# schematic.net
KiCad netlist of a schematic drawn in EAGLE
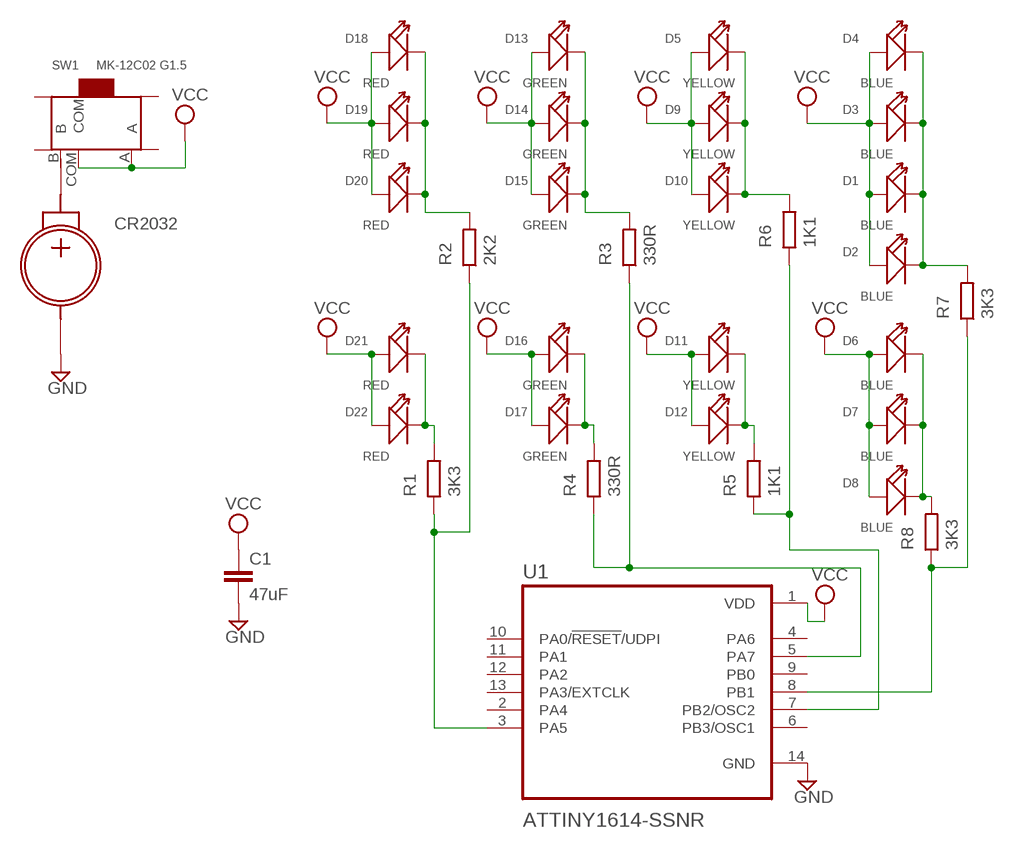
[diagram p0: schematic, sheet 1]

(export (version "E")
  (design (tool "Eeschema 10.0.6"))
  (components
    (comp (ref "C1")
      (value "47uF")
      (footprint "eagle-import:C1206")
      (libsource (lib "eagle-import") (part "C-EUC1206"))
    )
    (comp (ref "CR2032")
      (value "BS-7CR2032_COIN_CELL_BATTERY_HOLDER")
      (footprint "eagle-import:BS-7")
      (fields (field (name "MF") "MPD") (field (name "MP") "BS-7"))
      (libsource (lib "eagle-import") (part "BS-7CR2032_COIN_CELL_BATTERY_HOLDER"))
    )
    (comp (ref "D1")
      (value "BLUE")
      (footprint "eagle-import:LED2-2.54-D3.0MM")
      (fields (field (name "MPN") "CX-G302DC"))
      (libsource (lib "eagle-import") (part "DIP-LED-GREEN-GREEN(2P-D3MM)"))
    )
    (comp (ref "D2")
      (value "BLUE")
      (footprint "eagle-import:LED2-2.54-D3.0MM")
      (fields (field (name "MPN") "CX-G302DC"))
      (libsource (lib "eagle-import") (part "DIP-LED-GREEN-GREEN(2P-D3MM)"))
    )
    (comp (ref "D3")
      (value "BLUE")
      (footprint "eagle-import:LED2-2.54-D3.0MM")
      (fields (field (name "MPN") "CX-G302DC"))
      (libsource (lib "eagle-import") (part "DIP-LED-GREEN-GREEN(2P-D3MM)"))
    )
    (comp (ref "D4")
      (value "BLUE")
      (footprint "eagle-import:LED2-2.54-D3.0MM")
      (fields (field (name "MPN") "CX-G302DC"))
      (libsource (lib "eagle-import") (part "DIP-LED-GREEN-GREEN(2P-D3MM)"))
    )
    (comp (ref "D5")
      (value "YELLOW")
      (footprint "eagle-import:LED2-2.54-D3.0MM")
      (fields (field (name "MPN") "CX-G302DC"))
      (libsource (lib "eagle-import") (part "DIP-LED-GREEN-GREEN(2P-D3MM)"))
    )
    (comp (ref "D6")
      (value "BLUE")
      (footprint "eagle-import:LED2-2.54-D3.0MM")
      (fields (field (name "MPN") "CX-G302DC"))
      (libsource (lib "eagle-import") (part "DIP-LED-GREEN-GREEN(2P-D3MM)"))
    )
    (comp (ref "D7")
      (value "BLUE")
      (footprint "eagle-import:LED2-2.54-D3.0MM")
      (fields (field (name "MPN") "CX-G302DC"))
      (libsource (lib "eagle-import") (part "DIP-LED-GREEN-GREEN(2P-D3MM)"))
    )
    (comp (ref "D8")
      (value "BLUE")
      (footprint "eagle-import:LED2-2.54-D3.0MM")
      (fields (field (name "MPN") "CX-G302DC"))
      (libsource (lib "eagle-import") (part "DIP-LED-GREEN-GREEN(2P-D3MM)"))
    )
    (comp (ref "D9")
      (value "YELLOW")
      (footprint "eagle-import:LED2-2.54-D3.0MM")
      (fields (field (name "MPN") "CX-G302DC"))
      (libsource (lib "eagle-import") (part "DIP-LED-GREEN-GREEN(2P-D3MM)"))
    )
    (comp (ref "D10")
      (value "YELLOW")
      (footprint "eagle-import:LED2-2.54-D3.0MM")
      (fields (field (name "MPN") "CX-G302DC"))
      (libsource (lib "eagle-import") (part "DIP-LED-GREEN-GREEN(2P-D3MM)"))
    )
    (comp (ref "D11")
      (value "YELLOW")
      (footprint "eagle-import:LED2-2.54-D3.0MM")
      (fields (field (name "MPN") "CX-G302DC"))
      (libsource (lib "eagle-import") (part "DIP-LED-GREEN-GREEN(2P-D3MM)"))
    )
    (comp (ref "D12")
      (value "YELLOW")
      (footprint "eagle-import:LED2-2.54-D3.0MM")
      (fields (field (name "MPN") "CX-G302DC"))
      (libsource (lib "eagle-import") (part "DIP-LED-GREEN-GREEN(2P-D3MM)"))
    )
    (comp (ref "D13")
      (value "GREEN")
      (footprint "eagle-import:LED2-2.54-D3.0MM")
      (fields (field (name "MPN") "CX-G302DC"))
      (libsource (lib "eagle-import") (part "DIP-LED-GREEN-GREEN(2P-D3MM)"))
    )
    (comp (ref "D14")
      (value "GREEN")
      (footprint "eagle-import:LED2-2.54-D3.0MM")
      (fields (field (name "MPN") "CX-G302DC"))
      (libsource (lib "eagle-import") (part "DIP-LED-GREEN-GREEN(2P-D3MM)"))
    )
    (comp (ref "D15")
      (value "GREEN")
      (footprint "eagle-import:LED2-2.54-D3.0MM")
      (fields (field (name "MPN") "CX-G302DC"))
      (libsource (lib "eagle-import") (part "DIP-LED-GREEN-GREEN(2P-D3MM)"))
    )
    (comp (ref "D16")
      (value "GREEN")
      (footprint "eagle-import:LED2-2.54-D3.0MM")
      (fields (field (name "MPN") "CX-G302DC"))
      (libsource (lib "eagle-import") (part "DIP-LED-GREEN-GREEN(2P-D3MM)"))
    )
    (comp (ref "D17")
      (value "GREEN")
      (footprint "eagle-import:LED2-2.54-D3.0MM")
      (fields (field (name "MPN") "CX-G302DC"))
      (libsource (lib "eagle-import") (part "DIP-LED-GREEN-GREEN(2P-D3MM)"))
    )
    (comp (ref "D18")
      (value "RED")
      (footprint "eagle-import:LED2-2.54-D3.0MM")
      (fields (field (name "MPN") "CX-G302DC"))
      (libsource (lib "eagle-import") (part "DIP-LED-GREEN-GREEN(2P-D3MM)"))
    )
    (comp (ref "D19")
      (value "RED")
      (footprint "eagle-import:LED2-2.54-D3.0MM")
      (fields (field (name "MPN") "CX-G302DC"))
      (libsource (lib "eagle-import") (part "DIP-LED-GREEN-GREEN(2P-D3MM)"))
    )
    (comp (ref "D20")
      (value "RED")
      (footprint "eagle-import:LED2-2.54-D3.0MM")
      (fields (field (name "MPN") "CX-G302DC"))
      (libsource (lib "eagle-import") (part "DIP-LED-GREEN-GREEN(2P-D3MM)"))
    )
    (comp (ref "D21")
      (value "RED")
      (footprint "eagle-import:LED2-2.54-D3.0MM")
      (fields (field (name "MPN") "CX-G302DC"))
      (libsource (lib "eagle-import") (part "DIP-LED-GREEN-GREEN(2P-D3MM)"))
    )
    (comp (ref "D22")
      (value "RED")
      (footprint "eagle-import:LED2-2.54-D3.0MM")
      (fields (field (name "MPN") "CX-G302DC"))
      (libsource (lib "eagle-import") (part "DIP-LED-GREEN-GREEN(2P-D3MM)"))
    )
    (comp (ref "R1")
      (value "3K3")
      (footprint "eagle-import:RESAD724W46L381D178B")
      (libsource (lib "eagle-import") (part "RAXIAL-7.2MM-PITCH_"))
    )
    (comp (ref "R2")
      (value "2K2")
      (footprint "eagle-import:RESAD724W46L381D178B")
      (libsource (lib "eagle-import") (part "RAXIAL-7.2MM-PITCH_"))
    )
    (comp (ref "R3")
      (value "330R")
      (footprint "eagle-import:RESAD724W46L381D178B")
      (libsource (lib "eagle-import") (part "RAXIAL-7.2MM-PITCH_"))
    )
    (comp (ref "R4")
      (value "330R")
      (footprint "eagle-import:RESAD724W46L381D178B")
      (libsource (lib "eagle-import") (part "RAXIAL-7.2MM-PITCH_"))
    )
    (comp (ref "R5")
      (value "1K1")
      (footprint "eagle-import:RESAD724W46L381D178B")
      (libsource (lib "eagle-import") (part "RAXIAL-7.2MM-PITCH_"))
    )
    (comp (ref "R6")
      (value "1K1")
      (footprint "eagle-import:RESAD724W46L381D178B")
      (libsource (lib "eagle-import") (part "RAXIAL-7.2MM-PITCH_"))
    )
    (comp (ref "R7")
      (value "3K3")
      (footprint "eagle-import:RESAD724W46L381D178B")
      (libsource (lib "eagle-import") (part "RAXIAL-7.2MM-PITCH_"))
    )
    (comp (ref "R8")
      (value "3K3")
      (footprint "eagle-import:RESAD724W46L381D178B")
      (libsource (lib "eagle-import") (part "RAXIAL-7.2MM-PITCH_"))
    )
    (comp (ref "SW1")
      (value "MK-12C02 G1.5")
      (footprint "eagle-import:SW7-SMD-L6.7X2.7X3.2MM")
      (libsource (lib "eagle-import") (part "SMD-TOGGLE-SWITCH-ON-ON(3+4P-6.7X2.7MM)"))
    )
    (comp (ref "U1")
      (value "ATTINY1614-SSNR")
      (footprint "eagle-import:SOIC127P600X175-14N")
      (fields (field (name "MF") "Microchip"))
      (libsource (lib "eagle-import") (part "ATTINY1614-SSNR"))
    )
  )
  (nets
    (net (code "1") (name "/POS") (class "Default")
      (node (ref "CR2032") (pin "POS") (pinfunction "POS_POS") (pintype "power_in"))
    )
    (net (code "2") (name "GND") (class "Default")
      (node (ref "C1") (pin "2") (pinfunction "2_2") (pintype "passive"))
      (node (ref "CR2032") (pin "NEG") (pinfunction "NEG_NEG") (pintype "power_in"))
      (node (ref "U1") (pin "14") (pinfunction "GND_14") (pintype "power_in"))
    )
    (net (code "3") (name "Net-(D1--)") (class "Default")
      (node (ref "D1") (pin "K") (pinfunction "-_K") (pintype "passive"))
      (node (ref "D2") (pin "K") (pinfunction "-_K") (pintype "passive"))
      (node (ref "D3") (pin "K") (pinfunction "-_K") (pintype "passive"))
      (node (ref "D4") (pin "K") (pinfunction "-_K") (pintype "passive"))
      (node (ref "R7") (pin "2") (pinfunction "2_2") (pintype "passive"))
    )
    (net (code "4") (name "Net-(D6--)") (class "Default")
      (node (ref "D6") (pin "K") (pinfunction "-_K") (pintype "passive"))
      (node (ref "D7") (pin "K") (pinfunction "-_K") (pintype "passive"))
      (node (ref "D8") (pin "K") (pinfunction "-_K") (pintype "passive"))
      (node (ref "R8") (pin "2") (pinfunction "2_2") (pintype "passive"))
    )
    (net (code "5") (name "Net-(D10--)") (class "Default")
      (node (ref "D10") (pin "K") (pinfunction "-_K") (pintype "passive"))
      (node (ref "D5") (pin "K") (pinfunction "-_K") (pintype "passive"))
      (node (ref "D9") (pin "K") (pinfunction "-_K") (pintype "passive"))
      (node (ref "R6") (pin "2") (pinfunction "2_2") (pintype "passive"))
    )
    (net (code "6") (name "Net-(D11--)") (class "Default")
      (node (ref "D11") (pin "K") (pinfunction "-_K") (pintype "passive"))
      (node (ref "D12") (pin "K") (pinfunction "-_K") (pintype "passive"))
      (node (ref "R5") (pin "2") (pinfunction "2_2") (pintype "passive"))
    )
    (net (code "7") (name "Net-(D13--)") (class "Default")
      (node (ref "D13") (pin "K") (pinfunction "-_K") (pintype "passive"))
      (node (ref "D14") (pin "K") (pinfunction "-_K") (pintype "passive"))
      (node (ref "D15") (pin "K") (pinfunction "-_K") (pintype "passive"))
      (node (ref "R3") (pin "2") (pinfunction "2_2") (pintype "passive"))
    )
    (net (code "8") (name "Net-(D16--)") (class "Default")
      (node (ref "D16") (pin "K") (pinfunction "-_K") (pintype "passive"))
      (node (ref "D17") (pin "K") (pinfunction "-_K") (pintype "passive"))
      (node (ref "R4") (pin "2") (pinfunction "2_2") (pintype "passive"))
    )
    (net (code "9") (name "Net-(D18--)") (class "Default")
      (node (ref "D18") (pin "K") (pinfunction "-_K") (pintype "passive"))
      (node (ref "D19") (pin "K") (pinfunction "-_K") (pintype "passive"))
      (node (ref "D20") (pin "K") (pinfunction "-_K") (pintype "passive"))
      (node (ref "R2") (pin "2") (pinfunction "2_2") (pintype "passive"))
    )
    (net (code "10") (name "Net-(D21--)") (class "Default")
      (node (ref "D21") (pin "K") (pinfunction "-_K") (pintype "passive"))
      (node (ref "D22") (pin "K") (pinfunction "-_K") (pintype "passive"))
      (node (ref "R1") (pin "2") (pinfunction "2_2") (pintype "passive"))
    )
    (net (code "11") (name "Net-(U1-PA5)") (class "Default")
      (node (ref "R1") (pin "1") (pinfunction "1_1") (pintype "passive"))
      (node (ref "R2") (pin "1") (pinfunction "1_1") (pintype "passive"))
      (node (ref "U1") (pin "3") (pinfunction "PA5_3") (pintype "bidirectional"))
    )
    (net (code "12") (name "Net-(U1-PA7)") (class "Default")
      (node (ref "R3") (pin "1") (pinfunction "1_1") (pintype "passive"))
      (node (ref "R4") (pin "1") (pinfunction "1_1") (pintype "passive"))
      (node (ref "U1") (pin "5") (pinfunction "PA7_5") (pintype "bidirectional"))
    )
    (net (code "13") (name "Net-(U1-PB1)") (class "Default")
      (node (ref "R7") (pin "1") (pinfunction "1_1") (pintype "passive"))
      (node (ref "R8") (pin "1") (pinfunction "1_1") (pintype "passive"))
      (node (ref "U1") (pin "8") (pinfunction "PB1_8") (pintype "bidirectional"))
    )
    (net (code "14") (name "Net-(U1-PB2{slash}OSC2)") (class "Default")
      (node (ref "R5") (pin "1") (pinfunction "1_1") (pintype "passive"))
      (node (ref "R6") (pin "1") (pinfunction "1_1") (pintype "passive"))
      (node (ref "U1") (pin "7") (pinfunction "PB2/OSC2_7") (pintype "bidirectional"))
    )
    (net (code "15") (name "VCC") (class "Default")
      (node (ref "C1") (pin "1") (pinfunction "1_1") (pintype "passive"))
      (node (ref "D1") (pin "A") (pinfunction "+_A") (pintype "passive"))
      (node (ref "D10") (pin "A") (pinfunction "+_A") (pintype "passive"))
      (node (ref "D11") (pin "A") (pinfunction "+_A") (pintype "passive"))
      (node (ref "D12") (pin "A") (pinfunction "+_A") (pintype "passive"))
      (node (ref "D13") (pin "A") (pinfunction "+_A") (pintype "passive"))
      (node (ref "D14") (pin "A") (pinfunction "+_A") (pintype "passive"))
      (node (ref "D15") (pin "A") (pinfunction "+_A") (pintype "passive"))
      (node (ref "D16") (pin "A") (pinfunction "+_A") (pintype "passive"))
      (node (ref "D17") (pin "A") (pinfunction "+_A") (pintype "passive"))
      (node (ref "D18") (pin "A") (pinfunction "+_A") (pintype "passive"))
      (node (ref "D19") (pin "A") (pinfunction "+_A") (pintype "passive"))
      (node (ref "D2") (pin "A") (pinfunction "+_A") (pintype "passive"))
      (node (ref "D20") (pin "A") (pinfunction "+_A") (pintype "passive"))
      (node (ref "D21") (pin "A") (pinfunction "+_A") (pintype "passive"))
      (node (ref "D22") (pin "A") (pinfunction "+_A") (pintype "passive"))
      (node (ref "D3") (pin "A") (pinfunction "+_A") (pintype "passive"))
      (node (ref "D4") (pin "A") (pinfunction "+_A") (pintype "passive"))
      (node (ref "D5") (pin "A") (pinfunction "+_A") (pintype "passive"))
      (node (ref "D6") (pin "A") (pinfunction "+_A") (pintype "passive"))
      (node (ref "D7") (pin "A") (pinfunction "+_A") (pintype "passive"))
      (node (ref "D8") (pin "A") (pinfunction "+_A") (pintype "passive"))
      (node (ref "D9") (pin "A") (pinfunction "+_A") (pintype "passive"))
      (node (ref "SW1") (pin "A") (pinfunction "A_A") (pintype "bidirectional"))
      (node (ref "SW1") (pin "COM") (pinfunction "COM_COM") (pintype "bidirectional"))
      (node (ref "U1") (pin "1") (pinfunction "VDD_1") (pintype "power_in"))
    )
    (net (code "16") (name "unconnected-(SW1-PadB)") (class "Default")
      (node (ref "SW1") (pin "B") (pinfunction "B_B") (pintype "bidirectional"))
    )
    (net (code "17") (name "unconnected-(SW1-PadSS1)") (class "Default")
      (node (ref "SW1") (pin "SS1") (pinfunction "SS1_SS1") (pintype "bidirectional"))
    )
    (net (code "18") (name "unconnected-(SW1-PadSS2)") (class "Default")
      (node (ref "SW1") (pin "SS2") (pinfunction "SS2_SS2") (pintype "bidirectional"))
    )
    (net (code "19") (name "unconnected-(SW1-PadSS3)") (class "Default")
      (node (ref "SW1") (pin "SS3") (pinfunction "SS3_SS3") (pintype "bidirectional"))
    )
    (net (code "20") (name "unconnected-(SW1-PadSS4)") (class "Default")
      (node (ref "SW1") (pin "SS4") (pinfunction "SS4_SS4") (pintype "bidirectional"))
    )
    (net (code "21") (name "unconnected-(U1-PA0{slash}~{RESET}{slash}UDPI-Pad10)") (class "Default")
      (node (ref "U1") (pin "10") (pinfunction "PA0/~{RESET}/UDPI_10") (pintype "bidirectional"))
    )
    (net (code "22") (name "unconnected-(U1-PA1-Pad11)") (class "Default")
      (node (ref "U1") (pin "11") (pinfunction "PA1_11") (pintype "bidirectional"))
    )
    (net (code "23") (name "unconnected-(U1-PA2-Pad12)") (class "Default")
      (node (ref "U1") (pin "12") (pinfunction "PA2_12") (pintype "bidirectional"))
    )
    (net (code "24") (name "unconnected-(U1-PA3{slash}EXTCLK-Pad13)") (class "Default")
      (node (ref "U1") (pin "13") (pinfunction "PA3/EXTCLK_13") (pintype "bidirectional"))
    )
    (net (code "25") (name "unconnected-(U1-PA4-Pad2)") (class "Default")
      (node (ref "U1") (pin "2") (pinfunction "PA4_2") (pintype "bidirectional"))
    )
    (net (code "26") (name "unconnected-(U1-PA6-Pad4)") (class "Default")
      (node (ref "U1") (pin "4") (pinfunction "PA6_4") (pintype "bidirectional"))
    )
    (net (code "27") (name "unconnected-(U1-PB0-Pad9)") (class "Default")
      (node (ref "U1") (pin "9") (pinfunction "PB0_9") (pintype "bidirectional"))
    )
    (net (code "28") (name "unconnected-(U1-PB3{slash}OSC1-Pad6)") (class "Default")
      (node (ref "U1") (pin "6") (pinfunction "PB3/OSC1_6") (pintype "bidirectional"))
    )
  )
)
